# 3.net
KiCad netlist of a schematic drawn in Altium Designer
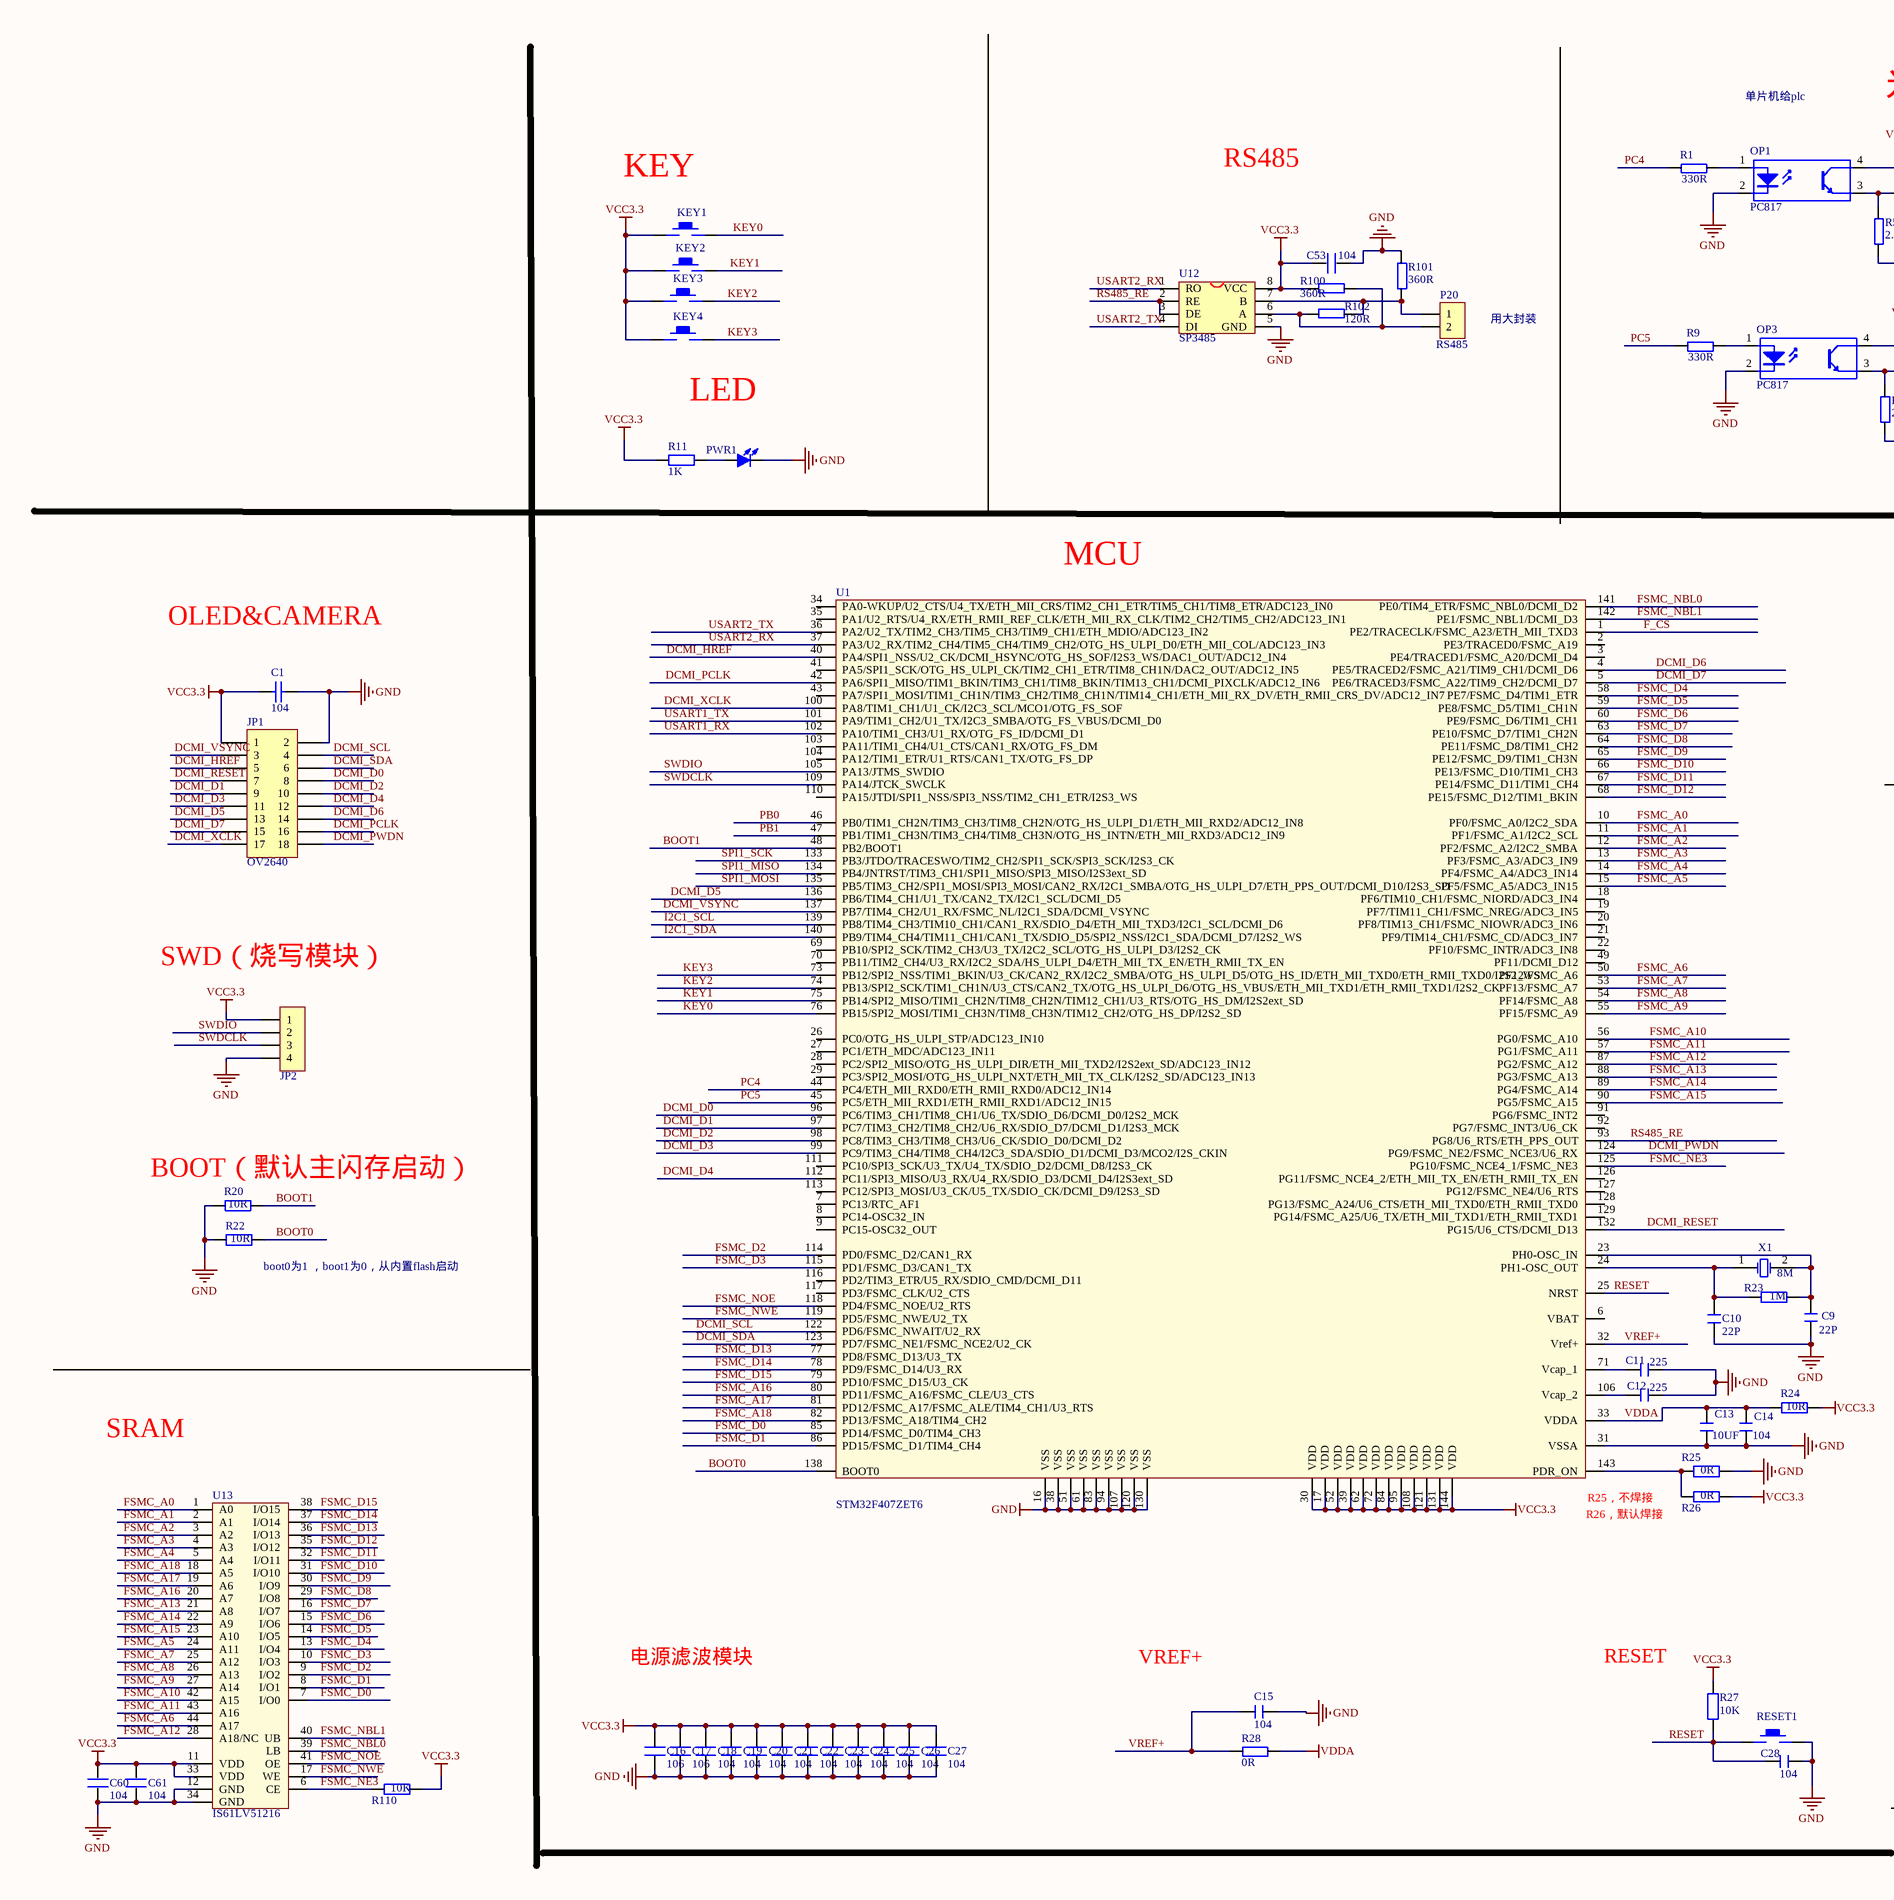
[diagram p0: 练一练3.SchDoc, left]
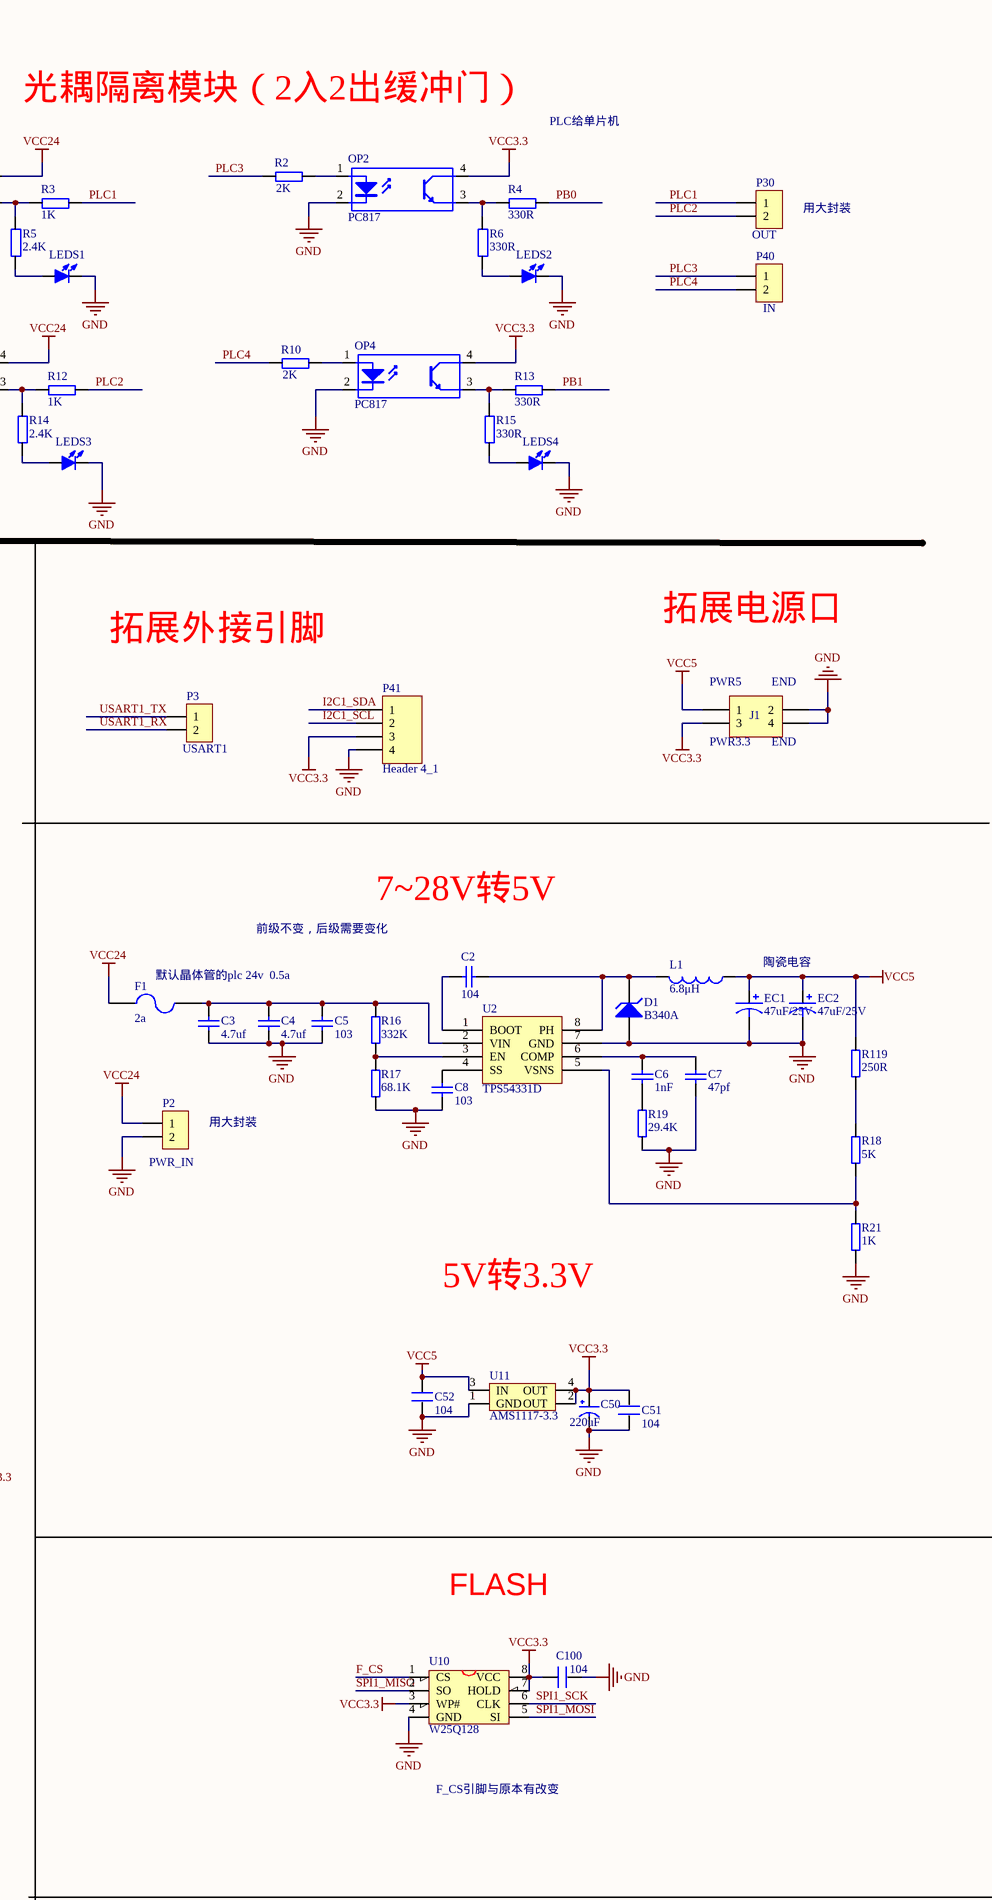
[diagram p1: 练一练3.SchDoc, right]

(export (version "E")
  (design (tool "Eeschema 10.0.6"))
  (components
    (comp (ref "C1")
      (value "104")
      (footprint "C0805 - duplicate")
      (description "Default Capacitor")
      (fields (field (name "PUBLISHER") "Altium Limited"))
      (libsource (lib "Lib_Devices_V1.0") (part "Cap0"))
    )
    (comp (ref "C2")
      (value "104")
      (footprint "C0805 - duplicate")
      (description "Default Capacitor")
      (fields (field (name "PUBLISHER") "Altium Limited"))
      (libsource (lib "Lib_Devices_V1.0") (part "Cap0"))
    )
    (comp (ref "C3")
      (value "4.7uf")
      (footprint "C0805 - duplicate")
      (description "Default Capacitor")
      (fields (field (name "PUBLISHER") "Altium Limited"))
      (libsource (lib "Lib_Devices_V1.0") (part "Cap0"))
    )
    (comp (ref "C4")
      (value "4.7uf")
      (footprint "C0805 - duplicate")
      (description "Default Capacitor")
      (fields (field (name "PUBLISHER") "Altium Limited"))
      (libsource (lib "Lib_Devices_V1.0") (part "Cap0"))
    )
    (comp (ref "C5")
      (value "103")
      (footprint "C0805 - duplicate")
      (description "Default Capacitor")
      (fields (field (name "PUBLISHER") "Altium Limited"))
      (libsource (lib "Lib_Devices_V1.0") (part "Cap0"))
    )
    (comp (ref "C6")
      (value "1nF")
      (footprint "C0805 - duplicate")
      (description "Default Capacitor")
      (fields (field (name "PUBLISHER") "Altium Limited"))
      (libsource (lib "Lib_Devices_V1.0") (part "Cap0"))
    )
    (comp (ref "C7")
      (value "47pf")
      (footprint "C0805 - duplicate")
      (description "Default Capacitor")
      (fields (field (name "PUBLISHER") "Altium Limited"))
      (libsource (lib "Lib_Devices_V1.0") (part "Cap0"))
    )
    (comp (ref "C8")
      (value "103")
      (footprint "C0805 - duplicate")
      (description "Default Capacitor")
      (fields (field (name "PUBLISHER") "Altium Limited"))
      (libsource (lib "Lib_Devices_V1.0") (part "Cap0"))
    )
    (comp (ref "C9")
      (value "22P")
      (footprint "C 0805")
      (description "无极性贴片电容")
      (fields (field (name "版权归属") "源创客"))
      (libsource (lib "STM32F407_CORE_BOARD") (part "C"))
    )
    (comp (ref "C10")
      (value "22P")
      (footprint "C 0805")
      (description "无极性贴片电容")
      (fields (field (name "版权归属") "源创客"))
      (libsource (lib "STM32F407_CORE_BOARD") (part "C"))
    )
    (comp (ref "C11")
      (value "225")
      (footprint "C 0805")
      (description "无极性贴片电容")
      (fields (field (name "版权归属") "源创客"))
      (libsource (lib "STM32F407_CORE_BOARD") (part "C"))
    )
    (comp (ref "C12")
      (value "225")
      (footprint "C 0805")
      (description "无极性贴片电容")
      (fields (field (name "版权归属") "源创客"))
      (libsource (lib "STM32F407_CORE_BOARD") (part "C"))
    )
    (comp (ref "C13")
      (value "10UF")
      (footprint "C 0805")
      (description "无极性贴片电容")
      (fields (field (name "版权归属") "源创客"))
      (libsource (lib "STM32F407_CORE_BOARD") (part "C"))
    )
    (comp (ref "C14")
      (value "104")
      (footprint "C 0805")
      (description "无极性贴片电容")
      (fields (field (name "版权归属") "源创客"))
      (libsource (lib "STM32F407_CORE_BOARD") (part "C"))
    )
    (comp (ref "C15")
      (value "104")
      (footprint "C 0805")
      (description "无极性贴片电容")
      (fields (field (name "版权归属") "源创客"))
      (libsource (lib "STM32F407_CORE_BOARD") (part "C"))
    )
    (comp (ref "C16")
      (value "106")
      (footprint "C 0805")
      (libsource (lib "Explorer STM32F407封装库_SCH") (part "C"))
    )
    (comp (ref "C17")
      (value "106")
      (footprint "C 0805")
      (libsource (lib "Explorer STM32F407封装库_SCH") (part "C"))
    )
    (comp (ref "C18")
      (value "104")
      (footprint "C 0805")
      (libsource (lib "Explorer STM32F407封装库_SCH") (part "C"))
    )
    (comp (ref "C19")
      (value "104")
      (footprint "C 0805")
      (libsource (lib "Explorer STM32F407封装库_SCH") (part "C"))
    )
    (comp (ref "C20")
      (value "104")
      (footprint "C 0805")
      (libsource (lib "Explorer STM32F407封装库_SCH") (part "C"))
    )
    (comp (ref "C21")
      (value "104")
      (footprint "C 0805")
      (libsource (lib "Explorer STM32F407封装库_SCH") (part "C"))
    )
    (comp (ref "C22")
      (value "104")
      (footprint "C 0805")
      (libsource (lib "Explorer STM32F407封装库_SCH") (part "C"))
    )
    (comp (ref "C23")
      (value "104")
      (footprint "C 0805")
      (libsource (lib "Explorer STM32F407封装库_SCH") (part "C"))
    )
    (comp (ref "C24")
      (value "104")
      (footprint "C 0805")
      (libsource (lib "Explorer STM32F407封装库_SCH") (part "C"))
    )
    (comp (ref "C25")
      (value "104")
      (footprint "C 0805")
      (libsource (lib "Explorer STM32F407封装库_SCH") (part "C"))
    )
    (comp (ref "C26")
      (value "104")
      (footprint "C 0805")
      (libsource (lib "Explorer STM32F407封装库_SCH") (part "C"))
    )
    (comp (ref "C27")
      (value "104")
      (footprint "C 0805")
      (libsource (lib "Explorer STM32F407封装库_SCH") (part "C"))
    )
    (comp (ref "C28")
      (value "104")
      (footprint "C 0805")
      (description "无极性贴片电容")
      (fields (field (name "版权归属") "源创客"))
      (libsource (lib "STM32F407_CORE_BOARD") (part "C"))
    )
    (comp (ref "C50") (value "220uF") (footprint "Cap_8_12") (libsource (lib "EXPLORER") (part "CAP")))
    (comp (ref "C51")
      (value "104")
      (footprint "C0805 - duplicate")
      (libsource (lib "Explorer STM32F407封装库2") (part "C"))
    )
    (comp (ref "C52")
      (value "104")
      (footprint "C0805 - duplicate")
      (libsource (lib "Explorer STM32F407封装库2") (part "C"))
    )
    (comp (ref "C53")
      (value "104")
      (footprint "C0805 - duplicate")
      (libsource (lib "Explorer STM32F407封装库2") (part "C"))
    )
    (comp (ref "C60")
      (value "104")
      (footprint "C 0805")
      (libsource (lib "Explorer STM32F407封装库_SCH") (part "C"))
    )
    (comp (ref "C61")
      (value "104")
      (footprint "C 0805")
      (libsource (lib "Explorer STM32F407封装库_SCH") (part "C"))
    )
    (comp (ref "C100")
      (value "104")
      (footprint "C0805 - duplicate")
      (libsource (lib "Explorer STM32F407封装库2") (part "C"))
    )
    (comp (ref "D1")
      (value "B340A")
      (footprint "DO-214AC")
      (description "瞬态抑制二极管")
      (fields (field (name "PUBLISHER") "Altium Limited"))
      (libsource (lib "Lib_Devices_V1.0") (part "D Zener"))
    )
    (comp (ref "EC1")
      (value "47uF/25V")
      (footprint "CAP_6.3*5MM")
      (description "Polarized Capacitor (Axial)")
      (fields (field (name "PUBLISHER") "Altium Limited"))
      (libsource (lib "Lib_Devices_V1.0") (part "Cap2"))
    )
    (comp (ref "EC2")
      (value "47uF/25V")
      (footprint "CAP_6.3*5MM")
      (description "Polarized Capacitor (Axial)")
      (fields (field (name "PUBLISHER") "Altium Limited"))
      (libsource (lib "Lib_Devices_V1.0") (part "Cap2"))
    )
    (comp (ref "F1")
      (value "2a")
      (footprint "fuse_big")
      (description "Fuse")
      (fields (field (name "PUBLISHER") "Altium Limited"))
      (libsource (lib "Lib_Devices_V1.0") (part "Fuse1"))
    )
    (comp (ref "J1")
      (value "PWR3.3       END")
      (footprint "HDR2X2")
      (description "Header, 2-Pin, Dual row")
      (fields (field (name "PUBLISHER") "Altium Limited"))
      (libsource (lib "练一练1") (part "Header 2X2"))
    )
    (comp (ref "JP1")
      (value "OV2640")
      (footprint "HDR2X9")
      (description "Header, 9-Pin, Dual row")
      (fields (field (name "PUBLISHER") "Altium Limited"))
      (libsource (lib "Miscellaneous Connectors") (part "Header 9X2"))
    )
    (comp (ref "JP2")
      (value "SWD")
      (footprint "HDR1X4")
      (description "4P接插件")
      (fields (field (name "版权归属") "源创客"))
      (libsource (lib "STM32F407_CORE_BOARD") (part "Header 4"))
    )
    (comp (ref "KEY1") (value "KEY_M") (footprint "KEY_4Pin") (libsource (lib "练一练1") (part "KEY_M")))
    (comp (ref "KEY2") (value "KEY_M") (footprint "KEY_4Pin") (libsource (lib "练一练1") (part "KEY_M")))
    (comp (ref "KEY3") (value "KEY_M") (footprint "KEY_4Pin") (libsource (lib "练一练1") (part "KEY_M")))
    (comp (ref "KEY4") (value "KEY_M") (footprint "KEY_4Pin") (libsource (lib "练一练1") (part "KEY_M")))
    (comp (ref "L1")
      (value "6.8μH")
      (footprint "Hunter")
      (description "Inductor")
      (fields (field (name "PUBLISHER") "Altium Limited"))
      (libsource (lib "Lib_Devices_V1.0") (part "Inductor"))
    )
    (comp (ref "LEDS1")
      (value "~")
      (footprint "LED_dp")
      (description "贴片LED")
      (fields (field (name "版权归属") "源创客"))
      (libsource (lib "STM32F407_CORE_BOARD") (part "LED-SMD"))
    )
    (comp (ref "LEDS2")
      (value "~")
      (footprint "LED_dp")
      (description "贴片LED")
      (fields (field (name "版权归属") "源创客"))
      (libsource (lib "STM32F407_CORE_BOARD") (part "LED-SMD"))
    )
    (comp (ref "LEDS3")
      (value "~")
      (footprint "LED_dp")
      (description "贴片LED")
      (fields (field (name "版权归属") "源创客"))
      (libsource (lib "STM32F407_CORE_BOARD") (part "LED-SMD"))
    )
    (comp (ref "LEDS4")
      (value "~")
      (footprint "LED_dp")
      (description "贴片LED")
      (fields (field (name "版权归属") "源创客"))
      (libsource (lib "STM32F407_CORE_BOARD") (part "LED-SMD"))
    )
    (comp (ref "OP1")
      (value "PC817")
      (footprint "SMD-4")
      (description "4-Pin Phototransistor Optocoupler")
      (fields (field (name "PUBLISHER") "Altium Limited"))
      (libsource (lib "练一练1") (part "Optoisolator"))
    )
    (comp (ref "OP2")
      (value "PC817")
      (footprint "SMD-4")
      (description "4-Pin Phototransistor Optocoupler")
      (fields (field (name "PUBLISHER") "Altium Limited"))
      (libsource (lib "练一练1") (part "Optoisolator"))
    )
    (comp (ref "OP3")
      (value "PC817")
      (footprint "SMD-4")
      (description "4-Pin Phototransistor Optocoupler")
      (fields (field (name "PUBLISHER") "Altium Limited"))
      (libsource (lib "Lib_Devices_V1.0") (part "Optoisolator"))
    )
    (comp (ref "OP4")
      (value "PC817")
      (footprint "SMD-4")
      (description "4-Pin Phototransistor Optocoupler")
      (fields (field (name "PUBLISHER") "Altium Limited"))
      (libsource (lib "Lib_Devices_V1.0") (part "Optoisolator"))
    )
    (comp (ref "P2") (value "PWR_IN") (footprint "HEAD2L-0.8") (libsource (lib "练一练1") (part "Header 1x2")))
    (comp (ref "P3") (value "USART1") (footprint "HDR1X2") (libsource (lib "练一练1") (part "Header 1x2")))
    (comp (ref "P20") (value "RS485") (footprint "HEAD2L-0.8") (libsource (lib "练一练1") (part "Header 1x2")))
    (comp (ref "P30") (value "OUT") (footprint "HEAD2L-0.8") (libsource (lib "练一练1") (part "Header 1x2")))
    (comp (ref "P40") (value "IN") (footprint "HEAD2L-0.8") (libsource (lib "练一练1") (part "Header 1x2")))
    (comp (ref "P41")
      (value "Header 4_1")
      (footprint "HDR1X4")
      (description "Header, 4-Pin")
      (fields (field (name "PUBLISHER") "Altium Limited"))
      (libsource (lib "STM32F407ZGT6-V3.0") (part "Header 4_1"))
    )
    (comp (ref "PWR1")
      (value "~")
      (footprint "LED_dp")
      (description "贴片LED")
      (fields (field (name "版权归属") "源创客"))
      (libsource (lib "STM32F407_CORE_BOARD") (part "LED-SMD"))
    )
    (comp (ref "R1") (value "330R") (footprint "R0805") (libsource (lib "练一练1") (part "R_1")))
    (comp (ref "R2") (value "2K") (footprint "R0805") (libsource (lib "练一练1") (part "R_1")))
    (comp (ref "R3") (value "1K") (footprint "R0805") (libsource (lib "练一练1") (part "R_3")))
    (comp (ref "R4") (value "330R") (footprint "R0805") (libsource (lib "练一练1") (part "R_3")))
    (comp (ref "R5") (value "2.4K") (footprint "R0805") (libsource (lib "练一练1") (part "R_3")))
    (comp (ref "R6") (value "330R") (footprint "R0805") (libsource (lib "练一练1") (part "R_3")))
    (comp (ref "R9") (value "330R") (footprint "R0805") (libsource (lib "练一练1") (part "R_1")))
    (comp (ref "R10") (value "2K") (footprint "R0805") (libsource (lib "练一练1") (part "R_1")))
    (comp (ref "R11")
      (value "1K")
      (footprint "r0805 - duplicate")
      (description "贴片电阻")
      (fields (field (name "版权归属") "源创客"))
      (libsource (lib "STM32F407_CORE_BOARD") (part "R"))
    )
    (comp (ref "R12") (value "1K") (footprint "R0805") (libsource (lib "练一练1") (part "R_3")))
    (comp (ref "R13") (value "330R") (footprint "R0805") (libsource (lib "练一练1") (part "R_3")))
    (comp (ref "R14") (value "2.4K") (footprint "R0805") (libsource (lib "练一练1") (part "R_3")))
    (comp (ref "R15") (value "330R") (footprint "R0805") (libsource (lib "练一练1") (part "R_3")))
    (comp (ref "R16")
      (value "332K")
      (footprint "R0805")
      (description "default resistor")
      (libsource (lib "Lib_Devices_V1.0") (part "Res0"))
    )
    (comp (ref "R17")
      (value "68.1K")
      (footprint "R0805")
      (description "default resistor")
      (libsource (lib "Lib_Devices_V1.0") (part "Res0"))
    )
    (comp (ref "R18")
      (value "5K")
      (footprint "R0805")
      (description "default resistor")
      (libsource (lib "Lib_Devices_V1.0") (part "Res0"))
    )
    (comp (ref "R19")
      (value "29.4K")
      (footprint "R0805")
      (description "default resistor")
      (libsource (lib "Lib_Devices_V1.0") (part "Res0"))
    )
    (comp (ref "R20")
      (value "10R")
      (footprint "R0805")
      (description "贴片电阻")
      (fields (field (name "版权归属") "源创客"))
      (libsource (lib "STM32F407_CORE_BOARD") (part "R"))
    )
    (comp (ref "R21")
      (value "1K")
      (footprint "R0805")
      (description "default resistor")
      (libsource (lib "Lib_Devices_V1.0") (part "Res0"))
    )
    (comp (ref "R22")
      (value "10R")
      (footprint "r0805 - duplicate")
      (description "贴片电阻")
      (fields (field (name "版权归属") "源创客"))
      (libsource (lib "STM32F407_CORE_BOARD") (part "R"))
    )
    (comp (ref "R23")
      (value "1M")
      (footprint "R 0805")
      (description "贴片电阻")
      (fields (field (name "版权归属") "源创客"))
      (libsource (lib "STM32F407_CORE_BOARD") (part "R"))
    )
    (comp (ref "R24")
      (value "10R")
      (footprint "R0805")
      (description "贴片电阻")
      (fields (field (name "版权归属") "源创客"))
      (libsource (lib "STM32F407_CORE_BOARD") (part "R"))
    )
    (comp (ref "R25")
      (value "0R")
      (footprint "r0805 - duplicate")
      (description "贴片电阻")
      (fields (field (name "版权归属") "源创客"))
      (libsource (lib "STM32F407_CORE_BOARD") (part "R"))
    )
    (comp (ref "R26")
      (value "0R")
      (footprint "r0805 - duplicate")
      (description "贴片电阻")
      (fields (field (name "版权归属") "源创客"))
      (libsource (lib "STM32F407_CORE_BOARD") (part "R"))
    )
    (comp (ref "R27")
      (value "10K")
      (footprint "R0805")
      (description "贴片电阻")
      (fields (field (name "版权归属") "源创客"))
      (libsource (lib "STM32F407_CORE_BOARD") (part "R"))
    )
    (comp (ref "R28") (value "0R") (footprint "r0805 - duplicate") (libsource (lib "练一练1") (part "R")))
    (comp (ref "R100")
      (value "360R")
      (footprint "R0805")
      (libsource (lib "Explorer STM32F407封装库2") (part "R"))
    )
    (comp (ref "R101")
      (value "360R")
      (footprint "R0805")
      (libsource (lib "Explorer STM32F407封装库2") (part "R"))
    )
    (comp (ref "R102")
      (value "120R")
      (footprint "R0805")
      (libsource (lib "Explorer STM32F407封装库2") (part "R"))
    )
    (comp (ref "R110")
      (value "10K")
      (footprint "r0805 - duplicate")
      (description "贴片电阻")
      (fields (field (name "版权归属") "源创客"))
      (libsource (lib "STM32F407_CORE_BOARD") (part "R"))
    )
    (comp (ref "R119")
      (value "250R")
      (footprint "R0805")
      (description "default resistor")
      (libsource (lib "Lib_Devices_V1.0") (part "Res0"))
    )
    (comp (ref "RESET1") (value "KEY_M") (footprint "KEY-SMD1") (libsource (lib "练一练1") (part "KEY_M")))
    (comp (ref "U1")
      (value "STM32F407ZET6")
      (footprint "LQFP144 20X20_M")
      (libsource (lib "STM32F407_CORE_BOARD") (part "STM32F407ZET6"))
    )
    (comp (ref "U2")
      (value "TPS54331D")
      (footprint "SOIC-8")
      (description "TPS54331DDAR")
      (libsource (lib "Camera_Detection") (part "TPS54331DDAR"))
    )
    (comp (ref "U10")
      (value "W25Q128")
      (footprint "SOIC-8")
      (description "W25X16;SST25VF016;MX25L1605")
      (libsource (lib "Explorer STM32F407封装库2") (part "W25X16"))
    )
    (comp (ref "U11")
      (value "AMS1117-3.3")
      (footprint "AMS1117")
      (libsource (lib "EXPLORER") (part "AMS1117"))
    )
    (comp (ref "U12")
      (value "SP3485")
      (footprint "SOP-8")
      (libsource (lib "Explorer STM32F407封装库2") (part "MAX3485"))
    )
    (comp (ref "U13")
      (value "IS61LV51216")
      (footprint "TSOP44_M")
      (description "SRAM芯片")
      (libsource (lib "STM32F407_CORE_BOARD") (part "IS61LV51216"))
    )
    (comp (ref "X1")
      (value "8M")
      (footprint "49/S_N")
      (description "Crystal Oscillator")
      (fields (field (name "PUBLISHER") "*"))
      (libsource (lib "练一练1") (part "XTAL"))
    )
  )
  (nets
    (net (code "1") (name "/BOOT0") (class "Default")
      (node (ref "R22") (pin "2") (pinfunction "2_2") (pintype "passive"))
      (node (ref "U1") (pin "138") (pinfunction "BOOT0_138") (pintype "passive"))
    )
    (net (code "2") (name "/BOOT1") (class "Default")
      (node (ref "R20") (pin "2") (pinfunction "2_2") (pintype "passive"))
      (node (ref "U1") (pin "48") (pinfunction "PB2/BOOT1_48") (pintype "passive"))
    )
    (net (code "3") (name "/DCMI_D0") (class "Default")
      (node (ref "JP1") (pin "8") (pinfunction "8_8") (pintype "passive"))
      (node (ref "U1") (pin "96") (pinfunction "PC6/TIM3_CH1/TIM8_CH1/U6_TX/SDIO_D6/DCMI_D0/I2S2_MCK_96") (pintype "passive"))
    )
    (net (code "4") (name "/DCMI_D1") (class "Default")
      (node (ref "JP1") (pin "9") (pinfunction "9_9") (pintype "passive"))
      (node (ref "U1") (pin "97") (pinfunction "PC7/TIM3_CH2/TIM8_CH2/U6_RX/SDIO_D7/DCMI_D1/I2S3_MCK_97") (pintype "passive"))
    )
    (net (code "5") (name "/DCMI_D2") (class "Default")
      (node (ref "JP1") (pin "10") (pinfunction "10_10") (pintype "passive"))
      (node (ref "U1") (pin "98") (pinfunction "PC8/TIM3_CH3/TIM8_CH3/U6_CK/SDIO_D0/DCMI_D2_98") (pintype "passive"))
    )
    (net (code "6") (name "/DCMI_D3") (class "Default")
      (node (ref "JP1") (pin "11") (pinfunction "11_11") (pintype "passive"))
      (node (ref "U1") (pin "99") (pinfunction "PC9/TIM3_CH4/TIM8_CH4/I2C3_SDA/SDIO_D1/DCMI_D3/MCO2/I2S_CKIN_99") (pintype "passive"))
    )
    (net (code "7") (name "/DCMI_D4") (class "Default")
      (node (ref "JP1") (pin "12") (pinfunction "12_12") (pintype "passive"))
      (node (ref "U1") (pin "112") (pinfunction "PC11/SPI3_MISO/U3_RX/U4_RX/SDIO_D3/DCMI_D4/I2S3ext_SD_112") (pintype "passive"))
    )
    (net (code "8") (name "/DCMI_D5") (class "Default")
      (node (ref "JP1") (pin "13") (pinfunction "13_13") (pintype "passive"))
      (node (ref "U1") (pin "136") (pinfunction "PB6/TIM4_CH1/U1_TX/CAN2_TX/I2C1_SCL/DCMI_D5_136") (pintype "passive"))
    )
    (net (code "9") (name "/DCMI_D6") (class "Default")
      (node (ref "JP1") (pin "14") (pinfunction "14_14") (pintype "passive"))
      (node (ref "U1") (pin "4") (pinfunction "PE5/TRACED2/FSMC_A21/TIM9_CH1/DCMI_D6_4") (pintype "passive"))
    )
    (net (code "10") (name "/DCMI_D7") (class "Default")
      (node (ref "JP1") (pin "15") (pinfunction "15_15") (pintype "passive"))
      (node (ref "U1") (pin "5") (pinfunction "PE6/TRACED3/FSMC_A22/TIM9_CH2/DCMI_D7_5") (pintype "passive"))
    )
    (net (code "11") (name "/DCMI_HREF") (class "Default")
      (node (ref "JP1") (pin "5") (pinfunction "5_5") (pintype "passive"))
      (node (ref "U1") (pin "40") (pinfunction "PA4/SPI1_NSS/U2_CK/DCMI_HSYNC/OTG_HS_SOF/I2S3_WS/DAC1_OUT/ADC12_IN4_40") (pintype "passive"))
    )
    (net (code "12") (name "/DCMI_PCLK") (class "Default")
      (node (ref "JP1") (pin "16") (pinfunction "16_16") (pintype "passive"))
      (node (ref "U1") (pin "42") (pinfunction "PA6/SPI1_MISO/TIM1_BKIN/TIM3_CH1/TIM8_BKIN/TIM13_CH1/DCMI_PIXCLK/ADC12_IN6_42") (pintype "passive"))
    )
    (net (code "13") (name "/DCMI_PWDN") (class "Default")
      (node (ref "JP1") (pin "18") (pinfunction "18_18") (pintype "passive"))
      (node (ref "U1") (pin "124") (pinfunction "PG9/FSMC_NE2/FSMC_NCE3/U6_RX_124") (pintype "passive"))
    )
    (net (code "14") (name "/DCMI_RESET") (class "Default")
      (node (ref "JP1") (pin "7") (pinfunction "7_7") (pintype "passive"))
      (node (ref "U1") (pin "132") (pinfunction "PG15/U6_CTS/DCMI_D13_132") (pintype "passive"))
    )
    (net (code "15") (name "/DCMI_SCL") (class "Default")
      (node (ref "JP1") (pin "4") (pinfunction "4_4") (pintype "passive"))
      (node (ref "U1") (pin "122") (pinfunction "PD6/FSMC_NWAIT/U2_RX_122") (pintype "passive"))
    )
    (net (code "16") (name "/DCMI_SDA") (class "Default")
      (node (ref "JP1") (pin "6") (pinfunction "6_6") (pintype "passive"))
      (node (ref "U1") (pin "123") (pinfunction "PD7/FSMC_NE1/FSMC_NCE2/U2_CK_123") (pintype "passive"))
    )
    (net (code "17") (name "/DCMI_VSYNC") (class "Default")
      (node (ref "JP1") (pin "3") (pinfunction "3_3") (pintype "passive"))
      (node (ref "U1") (pin "137") (pinfunction "PB7/TIM4_CH2/U1_RX/FSMC_NL/I2C1_SDA/DCMI_VSYNC_137") (pintype "passive"))
    )
    (net (code "18") (name "/DCMI_XCLK") (class "Default")
      (node (ref "JP1") (pin "17") (pinfunction "17_17") (pintype "passive"))
      (node (ref "U1") (pin "100") (pinfunction "PA8/TIM1_CH1/U1_CK/I2C3_SCL/MCO1/OTG_FS_SOF_100") (pintype "passive"))
    )
    (net (code "19") (name "/FSMC_A0") (class "Default")
      (node (ref "U1") (pin "10") (pinfunction "PF0/FSMC_A0/I2C2_SDA_10") (pintype "passive"))
      (node (ref "U13") (pin "1") (pinfunction "A0_1") (pintype "passive"))
    )
    (net (code "20") (name "/FSMC_A1") (class "Default")
      (node (ref "U1") (pin "11") (pinfunction "PF1/FSMC_A1/I2C2_SCL_11") (pintype "passive"))
      (node (ref "U13") (pin "2") (pinfunction "A1_2") (pintype "passive"))
    )
    (net (code "21") (name "/FSMC_A2") (class "Default")
      (node (ref "U1") (pin "12") (pinfunction "PF2/FSMC_A2/I2C2_SMBA_12") (pintype "passive"))
      (node (ref "U13") (pin "3") (pinfunction "A2_3") (pintype "passive"))
    )
    (net (code "22") (name "/FSMC_A3") (class "Default")
      (node (ref "U1") (pin "13") (pinfunction "PF3/FSMC_A3/ADC3_IN9_13") (pintype "passive"))
      (node (ref "U13") (pin "4") (pinfunction "A3_4") (pintype "passive"))
    )
    (net (code "23") (name "/FSMC_A4") (class "Default")
      (node (ref "U1") (pin "14") (pinfunction "PF4/FSMC_A4/ADC3_IN14_14") (pintype "passive"))
      (node (ref "U13") (pin "5") (pinfunction "A4_5") (pintype "passive"))
    )
    (net (code "24") (name "/FSMC_A5") (class "Default")
      (node (ref "U1") (pin "15") (pinfunction "PF5/FSMC_A5/ADC3_IN15_15") (pintype "passive"))
      (node (ref "U13") (pin "24") (pinfunction "A11_24") (pintype "passive"))
    )
    (net (code "25") (name "/FSMC_A6") (class "Default")
      (node (ref "U1") (pin "50") (pinfunction "PF12/FSMC_A6_50") (pintype "passive"))
      (node (ref "U13") (pin "44") (pinfunction "A17_44") (pintype "passive"))
    )
    (net (code "26") (name "/FSMC_A7") (class "Default")
      (node (ref "U1") (pin "53") (pinfunction "PF13/FSMC_A7_53") (pintype "passive"))
      (node (ref "U13") (pin "25") (pinfunction "A12_25") (pintype "passive"))
    )
    (net (code "27") (name "/FSMC_A8") (class "Default")
      (node (ref "U1") (pin "54") (pinfunction "PF14/FSMC_A8_54") (pintype "passive"))
      (node (ref "U13") (pin "26") (pinfunction "A13_26") (pintype "passive"))
    )
    (net (code "28") (name "/FSMC_A9") (class "Default")
      (node (ref "U1") (pin "55") (pinfunction "PF15/FSMC_A9_55") (pintype "passive"))
      (node (ref "U13") (pin "27") (pinfunction "A14_27") (pintype "passive"))
    )
    (net (code "29") (name "/FSMC_A10") (class "Default")
      (node (ref "U1") (pin "56") (pinfunction "PG0/FSMC_A10_56") (pintype "passive"))
      (node (ref "U13") (pin "42") (pinfunction "A15_42") (pintype "passive"))
    )
    (net (code "30") (name "/FSMC_A11") (class "Default")
      (node (ref "U1") (pin "57") (pinfunction "PG1/FSMC_A11_57") (pintype "passive"))
      (node (ref "U13") (pin "43") (pinfunction "A16_43") (pintype "passive"))
    )
    (net (code "31") (name "/FSMC_A12") (class "Default")
      (node (ref "U1") (pin "87") (pinfunction "PG2/FSMC_A12_87") (pintype "passive"))
      (node (ref "U13") (pin "28") (pinfunction "A18/NC_28") (pintype "passive"))
    )
    (net (code "32") (name "/FSMC_A13") (class "Default")
      (node (ref "U1") (pin "88") (pinfunction "PG3/FSMC_A13_88") (pintype "passive"))
      (node (ref "U13") (pin "21") (pinfunction "A8_21") (pintype "passive"))
    )
    (net (code "33") (name "/FSMC_A14") (class "Default")
      (node (ref "U1") (pin "89") (pinfunction "PG4/FSMC_A14_89") (pintype "passive"))
      (node (ref "U13") (pin "22") (pinfunction "A9_22") (pintype "passive"))
    )
    (net (code "34") (name "/FSMC_A15") (class "Default")
      (node (ref "U1") (pin "90") (pinfunction "PG5/FSMC_A15_90") (pintype "passive"))
      (node (ref "U13") (pin "23") (pinfunction "A10_23") (pintype "passive"))
    )
    (net (code "35") (name "/FSMC_A16") (class "Default")
      (node (ref "U1") (pin "80") (pinfunction "PD11/FSMC_A16/FSMC_CLE/U3_CTS_80") (pintype "passive"))
      (node (ref "U13") (pin "20") (pinfunction "A7_20") (pintype "passive"))
    )
    (net (code "36") (name "/FSMC_A17") (class "Default")
      (node (ref "U1") (pin "81") (pinfunction "PD12/FSMC_A17/FSMC_ALE/TIM4_CH1/U3_RTS_81") (pintype "passive"))
      (node (ref "U13") (pin "19") (pinfunction "A6_19") (pintype "passive"))
    )
    (net (code "37") (name "/FSMC_A18") (class "Default")
      (node (ref "U1") (pin "82") (pinfunction "PD13/FSMC_A18/TIM4_CH2_82") (pintype "passive"))
      (node (ref "U13") (pin "18") (pinfunction "A5_18") (pintype "passive"))
    )
    (net (code "38") (name "/FSMC_D0") (class "Default")
      (node (ref "U1") (pin "85") (pinfunction "PD14/FSMC_D0/TIM4_CH3_85") (pintype "passive"))
      (node (ref "U13") (pin "7") (pinfunction "I/O0_7") (pintype "passive"))
    )
    (net (code "39") (name "/FSMC_D1") (class "Default")
      (node (ref "U1") (pin "86") (pinfunction "PD15/FSMC_D1/TIM4_CH4_86") (pintype "passive"))
      (node (ref "U13") (pin "8") (pinfunction "I/O1_8") (pintype "passive"))
    )
    (net (code "40") (name "/FSMC_D2") (class "Default")
      (node (ref "U1") (pin "114") (pinfunction "PD0/FSMC_D2/CAN1_RX_114") (pintype "passive"))
      (node (ref "U13") (pin "9") (pinfunction "I/O2_9") (pintype "passive"))
    )
    (net (code "41") (name "/FSMC_D3") (class "Default")
      (node (ref "U1") (pin "115") (pinfunction "PD1/FSMC_D3/CAN1_TX_115") (pintype "passive"))
      (node (ref "U13") (pin "10") (pinfunction "I/O3_10") (pintype "passive"))
    )
    (net (code "42") (name "/FSMC_D4") (class "Default")
      (node (ref "U1") (pin "58") (pinfunction "PE7/FSMC_D4/TIM1_ETR_58") (pintype "passive"))
      (node (ref "U13") (pin "13") (pinfunction "I/O4_13") (pintype "passive"))
    )
    (net (code "43") (name "/FSMC_D5") (class "Default")
      (node (ref "U1") (pin "59") (pinfunction "PE8/FSMC_D5/TIM1_CH1N_59") (pintype "passive"))
      (node (ref "U13") (pin "14") (pinfunction "I/O5_14") (pintype "passive"))
    )
    (net (code "44") (name "/FSMC_D6") (class "Default")
      (node (ref "U1") (pin "60") (pinfunction "PE9/FSMC_D6/TIM1_CH1_60") (pintype "passive"))
      (node (ref "U13") (pin "15") (pinfunction "I/O6_15") (pintype "passive"))
    )
    (net (code "45") (name "/FSMC_D7") (class "Default")
      (node (ref "U1") (pin "63") (pinfunction "PE10/FSMC_D7/TIM1_CH2N_63") (pintype "passive"))
      (node (ref "U13") (pin "16") (pinfunction "I/O7_16") (pintype "passive"))
    )
    (net (code "46") (name "/FSMC_D8") (class "Default")
      (node (ref "U1") (pin "64") (pinfunction "PE11/FSMC_D8/TIM1_CH2_64") (pintype "passive"))
      (node (ref "U13") (pin "29") (pinfunction "I/O8_29") (pintype "passive"))
    )
    (net (code "47") (name "/FSMC_D9") (class "Default")
      (node (ref "U1") (pin "65") (pinfunction "PE12/FSMC_D9/TIM1_CH3N_65") (pintype "passive"))
      (node (ref "U13") (pin "30") (pinfunction "I/O9_30") (pintype "passive"))
    )
    (net (code "48") (name "/FSMC_D10") (class "Default")
      (node (ref "U1") (pin "66") (pinfunction "PE13/FSMC_D10/TIM1_CH3_66") (pintype "passive"))
      (node (ref "U13") (pin "31") (pinfunction "I/O10_31") (pintype "passive"))
    )
    (net (code "49") (name "/FSMC_D11") (class "Default")
      (node (ref "U1") (pin "67") (pinfunction "PE14/FSMC_D11/TIM1_CH4_67") (pintype "passive"))
      (node (ref "U13") (pin "32") (pinfunction "I/O11_32") (pintype "passive"))
    )
    (net (code "50") (name "/FSMC_D12") (class "Default")
      (node (ref "U1") (pin "68") (pinfunction "PE15/FSMC_D12/TIM1_BKIN_68") (pintype "passive"))
      (node (ref "U13") (pin "35") (pinfunction "I/O12_35") (pintype "passive"))
    )
    (net (code "51") (name "/FSMC_D13") (class "Default")
      (node (ref "U1") (pin "77") (pinfunction "PD8/FSMC_D13/U3_TX_77") (pintype "passive"))
      (node (ref "U13") (pin "36") (pinfunction "I/O13_36") (pintype "passive"))
    )
    (net (code "52") (name "/FSMC_D14") (class "Default")
      (node (ref "U1") (pin "78") (pinfunction "PD9/FSMC_D14/U3_RX_78") (pintype "passive"))
      (node (ref "U13") (pin "37") (pinfunction "I/O14_37") (pintype "passive"))
    )
    (net (code "53") (name "/FSMC_D15") (class "Default")
      (node (ref "U1") (pin "79") (pinfunction "PD10/FSMC_D15/U3_CK_79") (pintype "passive"))
      (node (ref "U13") (pin "38") (pinfunction "I/O15_38") (pintype "passive"))
    )
    (net (code "54") (name "/FSMC_NBL0") (class "Default")
      (node (ref "U1") (pin "141") (pinfunction "PE0/TIM4_ETR/FSMC_NBL0/DCMI_D2_141") (pintype "passive"))
      (node (ref "U13") (pin "39") (pinfunction "LB_39") (pintype "passive"))
    )
    (net (code "55") (name "/FSMC_NBL1") (class "Default")
      (node (ref "U1") (pin "142") (pinfunction "PE1/FSMC_NBL1/DCMI_D3_142") (pintype "passive"))
      (node (ref "U13") (pin "40") (pinfunction "UB_40") (pintype "passive"))
    )
    (net (code "56") (name "/FSMC_NE3") (class "Default")
      (node (ref "R110") (pin "1") (pinfunction "1_1") (pintype "passive"))
      (node (ref "U1") (pin "125") (pinfunction "PG10/FSMC_NCE4_1/FSMC_NE3_125") (pintype "passive"))
      (node (ref "U13") (pin "6") (pinfunction "CE_6") (pintype "passive"))
    )
    (net (code "57") (name "/FSMC_NOE") (class "Default")
      (node (ref "U1") (pin "118") (pinfunction "PD4/FSMC_NOE/U2_RTS_118") (pintype "passive"))
      (node (ref "U13") (pin "41") (pinfunction "OE_41") (pintype "passive"))
    )
    (net (code "58") (name "/FSMC_NWE") (class "Default")
      (node (ref "U1") (pin "119") (pinfunction "PD5/FSMC_NWE/U2_TX_119") (pintype "passive"))
      (node (ref "U13") (pin "17") (pinfunction "WE_17") (pintype "passive"))
    )
    (net (code "59") (name "/F_CS") (class "Default")
      (node (ref "U1") (pin "1") (pinfunction "PE2/TRACECLK/FSMC_A23/ETH_MII_TXD3_1") (pintype "passive"))
      (node (ref "U10") (pin "1") (pinfunction "CS_1") (pintype "passive"))
    )
    (net (code "60") (name "/I2C1_SCL") (class "Default")
      (node (ref "P41") (pin "2") (pinfunction "2_2") (pintype "passive"))
      (node (ref "U1") (pin "139") (pinfunction "PB8/TIM4_CH3/TIM10_CH1/CAN1_RX/SDIO_D4/ETH_MII_TXD3/I2C1_SCL/DCMI_D6_139") (pintype "passive"))
    )
    (net (code "61") (name "/I2C1_SDA") (class "Default")
      (node (ref "P41") (pin "1") (pinfunction "1_1") (pintype "passive"))
      (node (ref "U1") (pin "140") (pinfunction "PB9/TIM4_CH4/TIM11_CH1/CAN1_TX/SDIO_D5/SPI2_NSS/I2C1_SDA/DCMI_D7/I2S2_WS_140") (pintype "passive"))
    )
    (net (code "62") (name "/KEY0") (class "Default")
      (node (ref "KEY1") (pin "2") (pinfunction "2_2") (pintype "passive"))
      (node (ref "U1") (pin "76") (pinfunction "PB15/SPI2_MOSI/TIM1_CH3N/TIM8_CH3N/TIM12_CH2/OTG_HS_DP/I2S2_SD_76") (pintype "passive"))
    )
    (net (code "63") (name "/KEY1") (class "Default")
      (node (ref "KEY2") (pin "2") (pinfunction "2_2") (pintype "passive"))
      (node (ref "U1") (pin "75") (pinfunction "PB14/SPI2_MISO/TIM1_CH2N/TIM8_CH2N/TIM12_CH1/U3_RTS/OTG_HS_DM/I2S2ext_SD_75") (pintype "passive"))
    )
    (net (code "64") (name "/KEY2") (class "Default")
      (node (ref "KEY3") (pin "2") (pinfunction "2_2") (pintype "passive"))
      (node (ref "U1") (pin "74") (pinfunction "PB13/SPI2_SCK/TIM1_CH1N/U3_CTS/CAN2_TX/OTG_HS_ULPI_D6/OTG_HS_VBUS/ETH_MII_TXD1/ETH_RMII_TXD1/I2S2_CK_74") (pintype "passive"))
    )
    (net (code "65") (name "/KEY3") (class "Default")
      (node (ref "KEY4") (pin "2") (pinfunction "2_2") (pintype "passive"))
      (node (ref "U1") (pin "73") (pinfunction "PB12/SPI2_NSS/TIM1_BKIN/U3_CK/CAN2_RX/I2C2_SMBA/OTG_HS_ULPI_D5/OTG_HS_ID/ETH_MII_TXD0/ETH_RMII_TXD0/I2S2_WS_73") (pintype "passive"))
    )
    (net (code "66") (name "/PB0") (class "Default")
      (node (ref "R4") (pin "2") (pintype "passive"))
      (node (ref "U1") (pin "46") (pinfunction "PB0/TIM1_CH2N/TIM3_CH3/TIM8_CH2N/OTG_HS_ULPI_D1/ETH_MII_RXD2/ADC12_IN8_46") (pintype "passive"))
    )
    (net (code "67") (name "/PB1") (class "Default")
      (node (ref "R13") (pin "2") (pintype "passive"))
      (node (ref "U1") (pin "47") (pinfunction "PB1/TIM1_CH3N/TIM3_CH4/TIM8_CH3N/OTG_HS_INTN/ETH_MII_RXD3/ADC12_IN9_47") (pintype "passive"))
    )
    (net (code "68") (name "/PC4") (class "Default")
      (node (ref "R1") (pin "1") (pintype "passive"))
      (node (ref "U1") (pin "44") (pinfunction "PC4/ETH_MII_RXD0/ETH_RMII_RXD0/ADC12_IN14_44") (pintype "passive"))
    )
    (net (code "69") (name "/PC5") (class "Default")
      (node (ref "R9") (pin "1") (pintype "passive"))
      (node (ref "U1") (pin "45") (pinfunction "PC5/ETH_MII_RXD1/ETH_RMII_RXD1/ADC12_IN15_45") (pintype "passive"))
    )
    (net (code "70") (name "/PLC1") (class "Default")
      (node (ref "P30") (pin "1") (pinfunction "1_1") (pintype "passive"))
      (node (ref "R3") (pin "2") (pintype "passive"))
    )
    (net (code "71") (name "/PLC2") (class "Default")
      (node (ref "P30") (pin "2") (pinfunction "2_2") (pintype "passive"))
      (node (ref "R12") (pin "2") (pintype "passive"))
    )
    (net (code "72") (name "/PLC3") (class "Default")
      (node (ref "P40") (pin "1") (pinfunction "1_1") (pintype "passive"))
      (node (ref "R2") (pin "1") (pintype "passive"))
    )
    (net (code "73") (name "/PLC4") (class "Default")
      (node (ref "P40") (pin "2") (pinfunction "2_2") (pintype "passive"))
      (node (ref "R10") (pin "1") (pintype "passive"))
    )
    (net (code "74") (name "/RESET") (class "Default")
      (node (ref "C28") (pin "2") (pinfunction "2_2") (pintype "passive"))
      (node (ref "R27") (pin "1") (pinfunction "1_1") (pintype "passive"))
      (node (ref "RESET1") (pin "1") (pinfunction "1_1") (pintype "passive"))
      (node (ref "U1") (pin "25") (pinfunction "NRST_25") (pintype "passive"))
    )
    (net (code "75") (name "/RS485_RE") (class "Default")
      (node (ref "U1") (pin "93") (pinfunction "PG8/U6_RTS/ETH_PPS_OUT_93") (pintype "passive"))
      (node (ref "U12") (pin "2") (pinfunction "RE_2") (pintype "passive"))
      (node (ref "U12") (pin "3") (pinfunction "DE_3") (pintype "passive"))
    )
    (net (code "76") (name "/SPI1_MISO") (class "Default")
      (node (ref "U1") (pin "134") (pinfunction "PB4/JNTRST/TIM3_CH1/SPI1_MISO/SPI3_MISO/I2S3ext_SD_134") (pintype "passive"))
      (node (ref "U10") (pin "2") (pinfunction "SO_2") (pintype "passive"))
    )
    (net (code "77") (name "/SPI1_MOSI") (class "Default")
      (node (ref "U1") (pin "135") (pinfunction "PB5/TIM3_CH2/SPI1_MOSI/SPI3_MOSI/CAN2_RX/I2C1_SMBA/OTG_HS_ULPI_D7/ETH_PPS_OUT/DCMI_D10/I2S3_SD_135") (pintype "passive"))
      (node (ref "U10") (pin "5") (pinfunction "SI_5") (pintype "passive"))
    )
    (net (code "78") (name "/SPI1_SCK") (class "Default")
      (node (ref "U1") (pin "133") (pinfunction "PB3/JTDO/TRACESWO/TIM2_CH2/SPI1_SCK/SPI3_SCK/I2S3_CK_133") (pintype "passive"))
      (node (ref "U10") (pin "6") (pinfunction "CLK_6") (pintype "passive"))
    )
    (net (code "79") (name "/SWDCLK") (class "Default")
      (node (ref "JP2") (pin "3") (pinfunction "3_3") (pintype "passive"))
      (node (ref "U1") (pin "109") (pinfunction "PA14/JTCK_SWCLK_109") (pintype "passive"))
    )
    (net (code "80") (name "/SWDIO") (class "Default")
      (node (ref "JP2") (pin "2") (pinfunction "2_2") (pintype "passive"))
      (node (ref "U1") (pin "105") (pinfunction "PA13/JTMS_SWDIO_105") (pintype "passive"))
    )
    (net (code "81") (name "/USART1_RX") (class "Default")
      (node (ref "P3") (pin "2") (pinfunction "2_2") (pintype "passive"))
      (node (ref "U1") (pin "102") (pinfunction "PA10/TIM1_CH3/U1_RX/OTG_FS_ID/DCMI_D1_102") (pintype "passive"))
    )
    (net (code "82") (name "/USART1_TX") (class "Default")
      (node (ref "P3") (pin "1") (pinfunction "1_1") (pintype "passive"))
      (node (ref "U1") (pin "101") (pinfunction "PA9/TIM1_CH2/U1_TX/I2C3_SMBA/OTG_FS_VBUS/DCMI_D0_101") (pintype "passive"))
    )
    (net (code "83") (name "/USART2_RX") (class "Default")
      (node (ref "U1") (pin "37") (pinfunction "PA3/U2_RX/TIM2_CH4/TIM5_CH4/TIM9_CH2/OTG_HS_ULPI_D0/ETH_MII_COL/ADC123_IN3_37") (pintype "passive"))
      (node (ref "U12") (pin "1") (pinfunction "RO_1") (pintype "passive"))
    )
    (net (code "84") (name "/USART2_TX") (class "Default")
      (node (ref "U1") (pin "36") (pinfunction "PA2/U2_TX/TIM2_CH3/TIM5_CH3/TIM9_CH1/ETH_MDIO/ADC123_IN2_36") (pintype "passive"))
      (node (ref "U12") (pin "4") (pinfunction "DI_4") (pintype "passive"))
    )
    (net (code "85") (name "/VREF+") (class "Default")
      (node (ref "C15") (pin "2") (pinfunction "2_2") (pintype "passive"))
      (node (ref "R28") (pin "1") (pintype "passive"))
      (node (ref "U1") (pin "32") (pinfunction "Vref+_32") (pintype "passive"))
    )
    (net (code "86") (name "GND") (class "Default")
      (node (ref "C1") (pin "2") (pinfunction "2_2") (pintype "passive"))
      (node (ref "C10") (pin "1") (pinfunction "1_1") (pintype "passive"))
      (node (ref "C100") (pin "2") (pintype "passive"))
      (node (ref "C11") (pin "2") (pinfunction "2_2") (pintype "passive"))
      (node (ref "C12") (pin "2") (pinfunction "2_2") (pintype "passive"))
      (node (ref "C13") (pin "1") (pinfunction "1_1") (pintype "passive"))
      (node (ref "C14") (pin "1") (pinfunction "1_1") (pintype "passive"))
      (node (ref "C15") (pin "1") (pinfunction "1_1") (pintype "passive"))
      (node (ref "C16") (pin "1") (pintype "passive"))
      (node (ref "C17") (pin "1") (pintype "passive"))
      (node (ref "C18") (pin "1") (pintype "passive"))
      (node (ref "C19") (pin "1") (pintype "passive"))
      (node (ref "C20") (pin "1") (pintype "passive"))
      (node (ref "C21") (pin "1") (pintype "passive"))
      (node (ref "C22") (pin "1") (pintype "passive"))
      (node (ref "C23") (pin "1") (pintype "passive"))
      (node (ref "C24") (pin "1") (pintype "passive"))
      (node (ref "C25") (pin "1") (pintype "passive"))
      (node (ref "C26") (pin "1") (pintype "passive"))
      (node (ref "C27") (pin "1") (pintype "passive"))
      (node (ref "C28") (pin "1") (pinfunction "1_1") (pintype "passive"))
      (node (ref "C3") (pin "2") (pinfunction "2_2") (pintype "passive"))
      (node (ref "C4") (pin "2") (pinfunction "2_2") (pintype "passive"))
      (node (ref "C5") (pin "2") (pinfunction "2_2") (pintype "passive"))
      (node (ref "C50") (pin "2") (pinfunction "GND_2") (pintype "passive"))
      (node (ref "C51") (pin "1") (pintype "passive"))
      (node (ref "C52") (pin "1") (pintype "passive"))
      (node (ref "C53") (pin "2") (pintype "passive"))
      (node (ref "C60") (pin "1") (pintype "passive"))
      (node (ref "C61") (pin "1") (pintype "passive"))
      (node (ref "C7") (pin "2") (pinfunction "2_2") (pintype "passive"))
      (node (ref "C8") (pin "2") (pinfunction "2_2") (pintype "passive"))
      (node (ref "C9") (pin "1") (pinfunction "1_1") (pintype "passive"))
      (node (ref "D1") (pin "1") (pinfunction "A_1") (pintype "passive"))
      (node (ref "EC1") (pin "2") (pinfunction "2_2") (pintype "passive"))
      (node (ref "EC2") (pin "2") (pinfunction "2_2") (pintype "passive"))
      (node (ref "J1") (pin "2") (pinfunction "2_2") (pintype "passive"))
      (node (ref "J1") (pin "4") (pinfunction "4_4") (pintype "passive"))
      (node (ref "JP1") (pin "2") (pinfunction "2_2") (pintype "passive"))
      (node (ref "JP2") (pin "4") (pinfunction "4_4") (pintype "passive"))
      (node (ref "LEDS1") (pin "2") (pinfunction "K_2") (pintype "passive"))
      (node (ref "LEDS2") (pin "2") (pinfunction "K_2") (pintype "passive"))
      (node (ref "LEDS3") (pin "2") (pinfunction "K_2") (pintype "passive"))
      (node (ref "LEDS4") (pin "2") (pinfunction "K_2") (pintype "passive"))
      (node (ref "OP1") (pin "2") (pinfunction "K_2") (pintype "passive"))
      (node (ref "OP2") (pin "2") (pinfunction "K_2") (pintype "passive"))
      (node (ref "OP3") (pin "2") (pinfunction "K_2") (pintype "passive"))
      (node (ref "OP4") (pin "2") (pinfunction "K_2") (pintype "passive"))
      (node (ref "P2") (pin "2") (pinfunction "2_2") (pintype "passive"))
      (node (ref "P41") (pin "4") (pinfunction "4_4") (pintype "passive"))
      (node (ref "PWR1") (pin "2") (pinfunction "K_2") (pintype "passive"))
      (node (ref "R101") (pin "2") (pintype "passive"))
      (node (ref "R17") (pin "1") (pinfunction "1_1") (pintype "passive"))
      (node (ref "R19") (pin "2") (pinfunction "2_2") (pintype "passive"))
      (node (ref "R20") (pin "1") (pinfunction "1_1") (pintype "passive"))
      (node (ref "R21") (pin "1") (pinfunction "1_1") (pintype "passive"))
      (node (ref "R22") (pin "1") (pinfunction "1_1") (pintype "passive"))
      (node (ref "R25") (pin "2") (pinfunction "2_2") (pintype "passive"))
      (node (ref "RESET1") (pin "2") (pinfunction "2_2") (pintype "passive"))
      (node (ref "U1") (pin "107") (pinfunction "VSS_107") (pintype "passive"))
      (node (ref "U1") (pin "120") (pinfunction "VSS_120") (pintype "passive"))
      (node (ref "U1") (pin "130") (pinfunction "VSS_130") (pintype "passive"))
      (node (ref "U1") (pin "16") (pinfunction "VSS_16") (pintype "passive"))
      (node (ref "U1") (pin "31") (pinfunction "VSSA_31") (pintype "passive"))
      (node (ref "U1") (pin "38") (pinfunction "VSS_38") (pintype "passive"))
      (node (ref "U1") (pin "51") (pinfunction "VSS_51") (pintype "passive"))
      (node (ref "U1") (pin "61") (pinfunction "VSS_61") (pintype "passive"))
      (node (ref "U1") (pin "83") (pinfunction "VSS_83") (pintype "passive"))
      (node (ref "U1") (pin "94") (pinfunction "VSS_94") (pintype "passive"))
      (node (ref "U10") (pin "4") (pinfunction "GND_4") (pintype "passive"))
      (node (ref "U11") (pin "1") (pinfunction "GND_1") (pintype "passive"))
      (node (ref "U12") (pin "5") (pinfunction "GND_5") (pintype "passive"))
      (node (ref "U13") (pin "12") (pinfunction "GND_12") (pintype "passive"))
      (node (ref "U13") (pin "34") (pinfunction "GND_34") (pintype "passive"))
      (node (ref "U2") (pin "7") (pinfunction "GND_7") (pintype "passive"))
    )
    (net (code "87") (name "Net-(C6-Pad2)") (class "Default")
      (node (ref "C6") (pin "2") (pinfunction "2_2") (pintype "passive"))
      (node (ref "R19") (pin "1") (pinfunction "1_1") (pintype "passive"))
    )
    (net (code "88") (name "Net-(D1-K)") (class "Default")
      (node (ref "C2") (pin "2") (pinfunction "2_2") (pintype "passive"))
      (node (ref "D1") (pin "2") (pinfunction "K_2") (pintype "passive"))
      (node (ref "L1") (pin "2") (pinfunction "2_2") (pintype "passive"))
      (node (ref "U2") (pin "8") (pinfunction "PH_8") (pintype "passive"))
    )
    (net (code "89") (name "Net-(LEDS1-A)") (class "Default")
      (node (ref "LEDS1") (pin "1") (pinfunction "A_1") (pintype "passive"))
      (node (ref "R5") (pin "1") (pintype "passive"))
    )
    (net (code "90") (name "Net-(LEDS2-A)") (class "Default")
      (node (ref "LEDS2") (pin "1") (pinfunction "A_1") (pintype "passive"))
      (node (ref "R6") (pin "1") (pintype "passive"))
    )
    (net (code "91") (name "Net-(LEDS3-A)") (class "Default")
      (node (ref "LEDS3") (pin "1") (pinfunction "A_1") (pintype "passive"))
      (node (ref "R14") (pin "1") (pintype "passive"))
    )
    (net (code "92") (name "Net-(LEDS4-A)") (class "Default")
      (node (ref "LEDS4") (pin "1") (pinfunction "A_1") (pintype "passive"))
      (node (ref "R15") (pin "1") (pintype "passive"))
    )
    (net (code "93") (name "Net-(OP1-A)") (class "Default")
      (node (ref "OP1") (pin "1") (pinfunction "A_1") (pintype "passive"))
      (node (ref "R1") (pin "2") (pintype "passive"))
    )
    (net (code "94") (name "Net-(OP1-E)") (class "Default")
      (node (ref "OP1") (pin "3") (pinfunction "E_3") (pintype "passive"))
      (node (ref "R3") (pin "1") (pintype "passive"))
      (node (ref "R5") (pin "2") (pintype "passive"))
    )
    (net (code "95") (name "Net-(OP2-A)") (class "Default")
      (node (ref "OP2") (pin "1") (pinfunction "A_1") (pintype "passive"))
      (node (ref "R2") (pin "2") (pintype "passive"))
    )
    (net (code "96") (name "Net-(OP2-E)") (class "Default")
      (node (ref "OP2") (pin "3") (pinfunction "E_3") (pintype "passive"))
      (node (ref "R4") (pin "1") (pintype "passive"))
      (node (ref "R6") (pin "2") (pintype "passive"))
    )
    (net (code "97") (name "Net-(OP3-A)") (class "Default")
      (node (ref "OP3") (pin "1") (pinfunction "A_1") (pintype "passive"))
      (node (ref "R9") (pin "2") (pintype "passive"))
    )
    (net (code "98") (name "Net-(OP3-E)") (class "Default")
      (node (ref "OP3") (pin "3") (pinfunction "E_3") (pintype "passive"))
      (node (ref "R12") (pin "1") (pintype "passive"))
      (node (ref "R14") (pin "2") (pintype "passive"))
    )
    (net (code "99") (name "Net-(OP4-A)") (class "Default")
      (node (ref "OP4") (pin "1") (pinfunction "A_1") (pintype "passive"))
      (node (ref "R10") (pin "2") (pintype "passive"))
    )
    (net (code "100") (name "Net-(OP4-E)") (class "Default")
      (node (ref "OP4") (pin "3") (pinfunction "E_3") (pintype "passive"))
      (node (ref "R13") (pin "1") (pintype "passive"))
      (node (ref "R15") (pin "2") (pintype "passive"))
    )
    (net (code "101") (name "Net-(PWR1-A)") (class "Default")
      (node (ref "PWR1") (pin "1") (pinfunction "A_1") (pintype "passive"))
      (node (ref "R11") (pin "2") (pinfunction "2_2") (pintype "passive"))
    )
    (net (code "102") (name "Net-(R119-Pad1)") (class "Default")
      (node (ref "R119") (pin "1") (pinfunction "1_1") (pintype "passive"))
      (node (ref "R18") (pin "2") (pinfunction "2_2") (pintype "passive"))
    )
    (net (code "103") (name "Net-(U1-PDR_ON)") (class "Default")
      (node (ref "R25") (pin "1") (pinfunction "1_1") (pintype "passive"))
      (node (ref "R26") (pin "1") (pinfunction "1_1") (pintype "passive"))
      (node (ref "U1") (pin "143") (pinfunction "PDR_ON_143") (pintype "passive"))
    )
    (net (code "104") (name "Net-(U1-PH0-OSC_IN)") (class "Default")
      (node (ref "C9") (pin "2") (pinfunction "2_2") (pintype "passive"))
      (node (ref "R23") (pin "2") (pinfunction "2_2") (pintype "passive"))
      (node (ref "U1") (pin "23") (pinfunction "PH0-OSC_IN_23") (pintype "passive"))
      (node (ref "X1") (pin "2") (pinfunction "OSC2_2") (pintype "passive"))
    )
    (net (code "105") (name "Net-(U1-PH1-OSC_OUT)") (class "Default")
      (node (ref "C10") (pin "2") (pinfunction "2_2") (pintype "passive"))
      (node (ref "R23") (pin "1") (pinfunction "1_1") (pintype "passive"))
      (node (ref "U1") (pin "24") (pinfunction "PH1-OSC_OUT_24") (pintype "passive"))
      (node (ref "X1") (pin "1") (pinfunction "OSC1_1") (pintype "passive"))
    )
    (net (code "106") (name "Net-(U1-Vcap_1)") (class "Default")
      (node (ref "C11") (pin "1") (pinfunction "1_1") (pintype "passive"))
      (node (ref "U1") (pin "71") (pinfunction "Vcap_1_71") (pintype "passive"))
    )
    (net (code "107") (name "Net-(U1-Vcap_2)") (class "Default")
      (node (ref "C12") (pin "1") (pinfunction "1_1") (pintype "passive"))
      (node (ref "U1") (pin "106") (pinfunction "Vcap_2_106") (pintype "passive"))
    )
    (net (code "108") (name "Net-(U2-BOOT)") (class "Default")
      (node (ref "C2") (pin "1") (pinfunction "1_1") (pintype "passive"))
      (node (ref "U2") (pin "1") (pinfunction "BOOT_1") (pintype "passive"))
    )
    (net (code "109") (name "Net-(U2-COMP)") (class "Default")
      (node (ref "C6") (pin "1") (pinfunction "1_1") (pintype "passive"))
      (node (ref "C7") (pin "1") (pinfunction "1_1") (pintype "passive"))
      (node (ref "U2") (pin "6") (pinfunction "COMP_6") (pintype "passive"))
    )
    (net (code "110") (name "Net-(U2-EN)") (class "Default")
      (node (ref "R16") (pin "2") (pinfunction "2_2") (pintype "passive"))
      (node (ref "R17") (pin "2") (pinfunction "2_2") (pintype "passive"))
      (node (ref "U2") (pin "3") (pinfunction "EN_3") (pintype "passive"))
    )
    (net (code "111") (name "Net-(U2-SS)") (class "Default")
      (node (ref "C8") (pin "1") (pinfunction "1_1") (pintype "passive"))
      (node (ref "U2") (pin "4") (pinfunction "SS_4") (pintype "passive"))
    )
    (net (code "112") (name "Net-(U2-VIN)") (class "Default")
      (node (ref "C3") (pin "1") (pinfunction "1_1") (pintype "passive"))
      (node (ref "C4") (pin "1") (pinfunction "1_1") (pintype "passive"))
      (node (ref "C5") (pin "1") (pinfunction "1_1") (pintype "passive"))
      (node (ref "F1") (pin "2") (pinfunction "2_2") (pintype "passive"))
      (node (ref "R16") (pin "1") (pinfunction "1_1") (pintype "passive"))
      (node (ref "U2") (pin "2") (pinfunction "VIN_2") (pintype "passive"))
    )
    (net (code "113") (name "Net-(U2-VSNS)") (class "Default")
      (node (ref "R18") (pin "1") (pinfunction "1_1") (pintype "passive"))
      (node (ref "R21") (pin "2") (pinfunction "2_2") (pintype "passive"))
      (node (ref "U2") (pin "5") (pinfunction "VSNS_5") (pintype "passive"))
    )
    (net (code "114") (name "Net-(U12-A)") (class "Default")
      (node (ref "P20") (pin "2") (pinfunction "2_2") (pintype "passive"))
      (node (ref "R100") (pin "1") (pintype "passive"))
      (node (ref "R102") (pin "2") (pintype "passive"))
      (node (ref "U12") (pin "6") (pinfunction "A_6") (pintype "passive"))
    )
    (net (code "115") (name "Net-(U12-B)") (class "Default")
      (node (ref "P20") (pin "1") (pinfunction "1_1") (pintype "passive"))
      (node (ref "R101") (pin "1") (pintype "passive"))
      (node (ref "R102") (pin "1") (pintype "passive"))
      (node (ref "U12") (pin "7") (pinfunction "B_7") (pintype "passive"))
    )
    (net (code "116") (name "VCC3.3") (class "Default")
      (node (ref "C1") (pin "1") (pinfunction "1_1") (pintype "passive"))
      (node (ref "C100") (pin "1") (pintype "passive"))
      (node (ref "C16") (pin "2") (pintype "passive"))
      (node (ref "C17") (pin "2") (pintype "passive"))
      (node (ref "C18") (pin "2") (pintype "passive"))
      (node (ref "C19") (pin "2") (pintype "passive"))
      (node (ref "C20") (pin "2") (pintype "passive"))
      (node (ref "C21") (pin "2") (pintype "passive"))
      (node (ref "C22") (pin "2") (pintype "passive"))
      (node (ref "C23") (pin "2") (pintype "passive"))
      (node (ref "C24") (pin "2") (pintype "passive"))
      (node (ref "C25") (pin "2") (pintype "passive"))
      (node (ref "C26") (pin "2") (pintype "passive"))
      (node (ref "C27") (pin "2") (pintype "passive"))
      (node (ref "C50") (pin "1") (pinfunction "VCC_1") (pintype "passive"))
      (node (ref "C51") (pin "2") (pintype "passive"))
      (node (ref "C53") (pin "1") (pintype "passive"))
      (node (ref "C60") (pin "2") (pintype "passive"))
      (node (ref "C61") (pin "2") (pintype "passive"))
      (node (ref "J1") (pin "3") (pinfunction "3_3") (pintype "passive"))
      (node (ref "JP1") (pin "1") (pinfunction "1_1") (pintype "passive"))
      (node (ref "JP2") (pin "1") (pinfunction "1_1") (pintype "passive"))
      (node (ref "KEY1") (pin "1") (pinfunction "1_1") (pintype "passive"))
      (node (ref "KEY2") (pin "1") (pinfunction "1_1") (pintype "passive"))
      (node (ref "KEY3") (pin "1") (pinfunction "1_1") (pintype "passive"))
      (node (ref "KEY4") (pin "1") (pinfunction "1_1") (pintype "passive"))
      (node (ref "OP2") (pin "4") (pinfunction "C_4") (pintype "passive"))
      (node (ref "OP4") (pin "4") (pinfunction "C_4") (pintype "passive"))
      (node (ref "P41") (pin "3") (pinfunction "3_3") (pintype "passive"))
      (node (ref "R100") (pin "2") (pintype "passive"))
      (node (ref "R11") (pin "1") (pinfunction "1_1") (pintype "passive"))
      (node (ref "R110") (pin "2") (pinfunction "2_2") (pintype "passive"))
      (node (ref "R24") (pin "2") (pinfunction "2_2") (pintype "passive"))
      (node (ref "R26") (pin "2") (pinfunction "2_2") (pintype "passive"))
      (node (ref "R27") (pin "2") (pinfunction "2_2") (pintype "passive"))
      (node (ref "U1") (pin "108") (pinfunction "VDD_108") (pintype "passive"))
      (node (ref "U1") (pin "121") (pinfunction "VDD_121") (pintype "passive"))
      (node (ref "U1") (pin "131") (pinfunction "VDD_131") (pintype "passive"))
      (node (ref "U1") (pin "144") (pinfunction "VDD_144") (pintype "passive"))
      (node (ref "U1") (pin "17") (pinfunction "VDD_17") (pintype "passive"))
      (node (ref "U1") (pin "30") (pinfunction "VDD_30") (pintype "passive"))
      (node (ref "U1") (pin "39") (pinfunction "VDD_39") (pintype "passive"))
      (node (ref "U1") (pin "52") (pinfunction "VDD_52") (pintype "passive"))
      (node (ref "U1") (pin "62") (pinfunction "VDD_62") (pintype "passive"))
      (node (ref "U1") (pin "72") (pinfunction "VDD_72") (pintype "passive"))
      (node (ref "U1") (pin "84") (pinfunction "VDD_84") (pintype "passive"))
      (node (ref "U1") (pin "95") (pinfunction "VDD_95") (pintype "passive"))
      (node (ref "U10") (pin "3") (pinfunction "WP#_3") (pintype "passive"))
      (node (ref "U10") (pin "7") (pinfunction "HOLD_7") (pintype "passive"))
      (node (ref "U10") (pin "8") (pinfunction "VCC_8") (pintype "passive"))
      (node (ref "U11") (pin "2") (pinfunction "OUT_2") (pintype "passive"))
      (node (ref "U11") (pin "4") (pinfunction "OUT_4") (pintype "passive"))
      (node (ref "U12") (pin "8") (pinfunction "VCC_8") (pintype "passive"))
      (node (ref "U13") (pin "11") (pinfunction "VDD_11") (pintype "passive"))
      (node (ref "U13") (pin "33") (pinfunction "VDD_33") (pintype "passive"))
    )
    (net (code "117") (name "VCC5") (class "Default")
      (node (ref "C52") (pin "2") (pintype "passive"))
      (node (ref "EC1") (pin "1") (pinfunction "1_1") (pintype "passive"))
      (node (ref "EC2") (pin "1") (pinfunction "1_1") (pintype "passive"))
      (node (ref "J1") (pin "1") (pinfunction "1_1") (pintype "passive"))
      (node (ref "L1") (pin "1") (pinfunction "1_1") (pintype "passive"))
      (node (ref "R119") (pin "2") (pinfunction "2_2") (pintype "passive"))
      (node (ref "U11") (pin "3") (pinfunction "IN_3") (pintype "passive"))
    )
    (net (code "118") (name "VCC24") (class "Default")
      (node (ref "F1") (pin "1") (pinfunction "1_1") (pintype "passive"))
      (node (ref "OP1") (pin "4") (pinfunction "C_4") (pintype "passive"))
      (node (ref "OP3") (pin "4") (pinfunction "C_4") (pintype "passive"))
      (node (ref "P2") (pin "1") (pinfunction "1_1") (pintype "passive"))
    )
    (net (code "119") (name "VDDA") (class "Default")
      (node (ref "C13") (pin "2") (pinfunction "2_2") (pintype "passive"))
      (node (ref "C14") (pin "2") (pinfunction "2_2") (pintype "passive"))
      (node (ref "R24") (pin "1") (pinfunction "1_1") (pintype "passive"))
      (node (ref "R28") (pin "2") (pintype "passive"))
      (node (ref "U1") (pin "33") (pinfunction "VDDA_33") (pintype "passive"))
    )
    (net (code "120") (name "unconnected-(U1-PA0-WKUP{slash}U2_CTS{slash}U4_TX{slash}ETH_MII_CRS{slash}TIM2_CH1_ETR{slash}TIM5_CH1{slash}TIM8_ETR{slash}ADC123_IN0-Pad34)") (class "Default")
      (node (ref "U1") (pin "34") (pinfunction "PA0-WKUP/U2_CTS/U4_TX/ETH_MII_CRS/TIM2_CH1_ETR/TIM5_CH1/TIM8_ETR/ADC123_IN0_34") (pintype "passive"))
    )
    (net (code "121") (name "unconnected-(U1-PA1{slash}U2_RTS{slash}U4_RX{slash}ETH_RMII_REF_CLK{slash}ETH_MII_RX_CLK{slash}TIM2_CH2{slash}TIM5_CH2{slash}ADC123_IN1-Pad35)") (class "Default")
      (node (ref "U1") (pin "35") (pinfunction "PA1/U2_RTS/U4_RX/ETH_RMII_REF_CLK/ETH_MII_RX_CLK/TIM2_CH2/TIM5_CH2/ADC123_IN1_35") (pintype "passive"))
    )
    (net (code "122") (name "unconnected-(U1-PA5{slash}SPI1_SCK{slash}OTG_HS_ULPI_CK{slash}TIM2_CH1_ETR{slash}TIM8_CH1N{slash}DAC2_OUT{slash}ADC12_IN5-Pad41)") (class "Default")
      (node (ref "U1") (pin "41") (pinfunction "PA5/SPI1_SCK/OTG_HS_ULPI_CK/TIM2_CH1_ETR/TIM8_CH1N/DAC2_OUT/ADC12_IN5_41") (pintype "passive"))
    )
    (net (code "123") (name "unconnected-(U1-PA7{slash}SPI1_MOSI{slash}TIM1_CH1N{slash}TIM3_CH2{slash}TIM8_CH1N{slash}TIM14_CH1{slash}ETH_MII_RX_DV{slash}ETH_RMII_CRS_DV{slash}ADC12_IN7-Pad43)") (class "Default")
      (node (ref "U1") (pin "43") (pinfunction "PA7/SPI1_MOSI/TIM1_CH1N/TIM3_CH2/TIM8_CH1N/TIM14_CH1/ETH_MII_RX_DV/ETH_RMII_CRS_DV/ADC12_IN7_43") (pintype "passive"))
    )
    (net (code "124") (name "unconnected-(U1-PA11{slash}TIM1_CH4{slash}U1_CTS{slash}CAN1_RX{slash}OTG_FS_DM-Pad103)") (class "Default")
      (node (ref "U1") (pin "103") (pinfunction "PA11/TIM1_CH4/U1_CTS/CAN1_RX/OTG_FS_DM_103") (pintype "passive"))
    )
    (net (code "125") (name "unconnected-(U1-PA12{slash}TIM1_ETR{slash}U1_RTS{slash}CAN1_TX{slash}OTG_FS_DP-Pad104)") (class "Default")
      (node (ref "U1") (pin "104") (pinfunction "PA12/TIM1_ETR/U1_RTS/CAN1_TX/OTG_FS_DP_104") (pintype "passive"))
    )
    (net (code "126") (name "unconnected-(U1-PA15{slash}JTDI{slash}SPI1_NSS{slash}SPI3_NSS{slash}TIM2_CH1_ETR{slash}I2S3_WS-Pad110)") (class "Default")
      (node (ref "U1") (pin "110") (pinfunction "PA15/JTDI/SPI1_NSS/SPI3_NSS/TIM2_CH1_ETR/I2S3_WS_110") (pintype "passive"))
    )
    (net (code "127") (name "unconnected-(U1-PB10{slash}SPI2_SCK{slash}TIM2_CH3{slash}U3_TX{slash}I2C2_SCL{slash}OTG_HS_ULPI_D3{slash}I2S2_CK-Pad69)") (class "Default")
      (node (ref "U1") (pin "69") (pinfunction "PB10/SPI2_SCK/TIM2_CH3/U3_TX/I2C2_SCL/OTG_HS_ULPI_D3/I2S2_CK_69") (pintype "passive"))
    )
    (net (code "128") (name "unconnected-(U1-PB11{slash}TIM2_CH4{slash}U3_RX{slash}I2C2_SDA{slash}HS_ULPI_D4{slash}ETH_MII_TX_EN{slash}ETH_RMII_TX_EN-Pad70)") (class "Default")
      (node (ref "U1") (pin "70") (pinfunction "PB11/TIM2_CH4/U3_RX/I2C2_SDA/HS_ULPI_D4/ETH_MII_TX_EN/ETH_RMII_TX_EN_70") (pintype "passive"))
    )
    (net (code "129") (name "unconnected-(U1-PC0{slash}OTG_HS_ULPI_STP{slash}ADC123_IN10-Pad26)") (class "Default")
      (node (ref "U1") (pin "26") (pinfunction "PC0/OTG_HS_ULPI_STP/ADC123_IN10_26") (pintype "passive"))
    )
    (net (code "130") (name "unconnected-(U1-PC1{slash}ETH_MDC{slash}ADC123_IN11-Pad27)") (class "Default")
      (node (ref "U1") (pin "27") (pinfunction "PC1/ETH_MDC/ADC123_IN11_27") (pintype "passive"))
    )
    (net (code "131") (name "unconnected-(U1-PC2{slash}SPI2_MISO{slash}OTG_HS_ULPI_DIR{slash}ETH_MII_TXD2{slash}I2S2ext_SD{slash}ADC123_IN12-Pad28)") (class "Default")
      (node (ref "U1") (pin "28") (pinfunction "PC2/SPI2_MISO/OTG_HS_ULPI_DIR/ETH_MII_TXD2/I2S2ext_SD/ADC123_IN12_28") (pintype "passive"))
    )
    (net (code "132") (name "unconnected-(U1-PC3{slash}SPI2_MOSI{slash}OTG_HS_ULPI_NXT{slash}ETH_MII_TX_CLK{slash}I2S2_SD{slash}ADC123_IN13-Pad29)") (class "Default")
      (node (ref "U1") (pin "29") (pinfunction "PC3/SPI2_MOSI/OTG_HS_ULPI_NXT/ETH_MII_TX_CLK/I2S2_SD/ADC123_IN13_29") (pintype "passive"))
    )
    (net (code "133") (name "unconnected-(U1-PC10{slash}SPI3_SCK{slash}U3_TX{slash}U4_TX{slash}SDIO_D2{slash}DCMI_D8{slash}I2S3_CK-Pad111)") (class "Default")
      (node (ref "U1") (pin "111") (pinfunction "PC10/SPI3_SCK/U3_TX/U4_TX/SDIO_D2/DCMI_D8/I2S3_CK_111") (pintype "passive"))
    )
    (net (code "134") (name "unconnected-(U1-PC12{slash}SPI3_MOSI{slash}U3_CK{slash}U5_TX{slash}SDIO_CK{slash}DCMI_D9{slash}I2S3_SD-Pad113)") (class "Default")
      (node (ref "U1") (pin "113") (pinfunction "PC12/SPI3_MOSI/U3_CK/U5_TX/SDIO_CK/DCMI_D9/I2S3_SD_113") (pintype "passive"))
    )
    (net (code "135") (name "unconnected-(U1-PC13{slash}RTC_AF1-Pad7)") (class "Default")
      (node (ref "U1") (pin "7") (pinfunction "PC13/RTC_AF1_7") (pintype "passive"))
    )
    (net (code "136") (name "unconnected-(U1-PC14-OSC32_IN-Pad8)") (class "Default")
      (node (ref "U1") (pin "8") (pinfunction "PC14-OSC32_IN_8") (pintype "passive"))
    )
    (net (code "137") (name "unconnected-(U1-PC15-OSC32_OUT-Pad9)") (class "Default")
      (node (ref "U1") (pin "9") (pinfunction "PC15-OSC32_OUT_9") (pintype "passive"))
    )
    (net (code "138") (name "unconnected-(U1-PD2{slash}TIM3_ETR{slash}U5_RX{slash}SDIO_CMD{slash}DCMI_D11-Pad116)") (class "Default")
      (node (ref "U1") (pin "116") (pinfunction "PD2/TIM3_ETR/U5_RX/SDIO_CMD/DCMI_D11_116") (pintype "passive"))
    )
    (net (code "139") (name "unconnected-(U1-PD3{slash}FSMC_CLK{slash}U2_CTS-Pad117)") (class "Default")
      (node (ref "U1") (pin "117") (pinfunction "PD3/FSMC_CLK/U2_CTS_117") (pintype "passive"))
    )
    (net (code "140") (name "unconnected-(U1-PE3{slash}TRACED0{slash}FSMC_A19-Pad2)") (class "Default")
      (node (ref "U1") (pin "2") (pinfunction "PE3/TRACED0/FSMC_A19_2") (pintype "passive"))
    )
    (net (code "141") (name "unconnected-(U1-PE4{slash}TRACED1{slash}FSMC_A20{slash}DCMI_D4-Pad3)") (class "Default")
      (node (ref "U1") (pin "3") (pinfunction "PE4/TRACED1/FSMC_A20/DCMI_D4_3") (pintype "passive"))
    )
    (net (code "142") (name "unconnected-(U1-PF6{slash}TIM10_CH1{slash}FSMC_NIORD{slash}ADC3_IN4-Pad18)") (class "Default")
      (node (ref "U1") (pin "18") (pinfunction "PF6/TIM10_CH1/FSMC_NIORD/ADC3_IN4_18") (pintype "passive"))
    )
    (net (code "143") (name "unconnected-(U1-PF7{slash}TIM11_CH1{slash}FSMC_NREG{slash}ADC3_IN5-Pad19)") (class "Default")
      (node (ref "U1") (pin "19") (pinfunction "PF7/TIM11_CH1/FSMC_NREG/ADC3_IN5_19") (pintype "passive"))
    )
    (net (code "144") (name "unconnected-(U1-PF8{slash}TIM13_CH1{slash}FSMC_NIOWR{slash}ADC3_IN6-Pad20)") (class "Default")
      (node (ref "U1") (pin "20") (pinfunction "PF8/TIM13_CH1/FSMC_NIOWR/ADC3_IN6_20") (pintype "passive"))
    )
    (net (code "145") (name "unconnected-(U1-PF9{slash}TIM14_CH1{slash}FSMC_CD{slash}ADC3_IN7-Pad21)") (class "Default")
      (node (ref "U1") (pin "21") (pinfunction "PF9/TIM14_CH1/FSMC_CD/ADC3_IN7_21") (pintype "passive"))
    )
    (net (code "146") (name "unconnected-(U1-PF10{slash}FSMC_INTR{slash}ADC3_IN8-Pad22)") (class "Default")
      (node (ref "U1") (pin "22") (pinfunction "PF10/FSMC_INTR/ADC3_IN8_22") (pintype "passive"))
    )
    (net (code "147") (name "unconnected-(U1-PF11{slash}DCMI_D12-Pad49)") (class "Default")
      (node (ref "U1") (pin "49") (pinfunction "PF11/DCMI_D12_49") (pintype "passive"))
    )
    (net (code "148") (name "unconnected-(U1-PG6{slash}FSMC_INT2-Pad91)") (class "Default")
      (node (ref "U1") (pin "91") (pinfunction "PG6/FSMC_INT2_91") (pintype "passive"))
    )
    (net (code "149") (name "unconnected-(U1-PG7{slash}FSMC_INT3{slash}U6_CK-Pad92)") (class "Default")
      (node (ref "U1") (pin "92") (pinfunction "PG7/FSMC_INT3/U6_CK_92") (pintype "passive"))
    )
    (net (code "150") (name "unconnected-(U1-PG11{slash}FSMC_NCE4_2{slash}ETH_MII_TX_EN{slash}ETH_RMII_TX_EN-Pad126)") (class "Default")
      (node (ref "U1") (pin "126") (pinfunction "PG11/FSMC_NCE4_2/ETH_MII_TX_EN/ETH_RMII_TX_EN_126") (pintype "passive"))
    )
    (net (code "151") (name "unconnected-(U1-PG12{slash}FSMC_NE4{slash}U6_RTS-Pad127)") (class "Default")
      (node (ref "U1") (pin "127") (pinfunction "PG12/FSMC_NE4/U6_RTS_127") (pintype "passive"))
    )
    (net (code "152") (name "unconnected-(U1-PG13{slash}FSMC_A24{slash}U6_CTS{slash}ETH_MII_TXD0{slash}ETH_RMII_TXD0-Pad128)") (class "Default")
      (node (ref "U1") (pin "128") (pinfunction "PG13/FSMC_A24/U6_CTS/ETH_MII_TXD0/ETH_RMII_TXD0_128") (pintype "passive"))
    )
    (net (code "153") (name "unconnected-(U1-PG14{slash}FSMC_A25{slash}U6_TX{slash}ETH_MII_TXD1{slash}ETH_RMII_TXD1-Pad129)") (class "Default")
      (node (ref "U1") (pin "129") (pinfunction "PG14/FSMC_A25/U6_TX/ETH_MII_TXD1/ETH_RMII_TXD1_129") (pintype "passive"))
    )
    (net (code "154") (name "unconnected-(U1-VBAT-Pad6)") (class "Default")
      (node (ref "U1") (pin "6") (pinfunction "VBAT_6") (pintype "passive"))
    )
  )
)
